# 48V-5V_Buck.net
KiCad netlist of a schematic drawn in Altium Designer
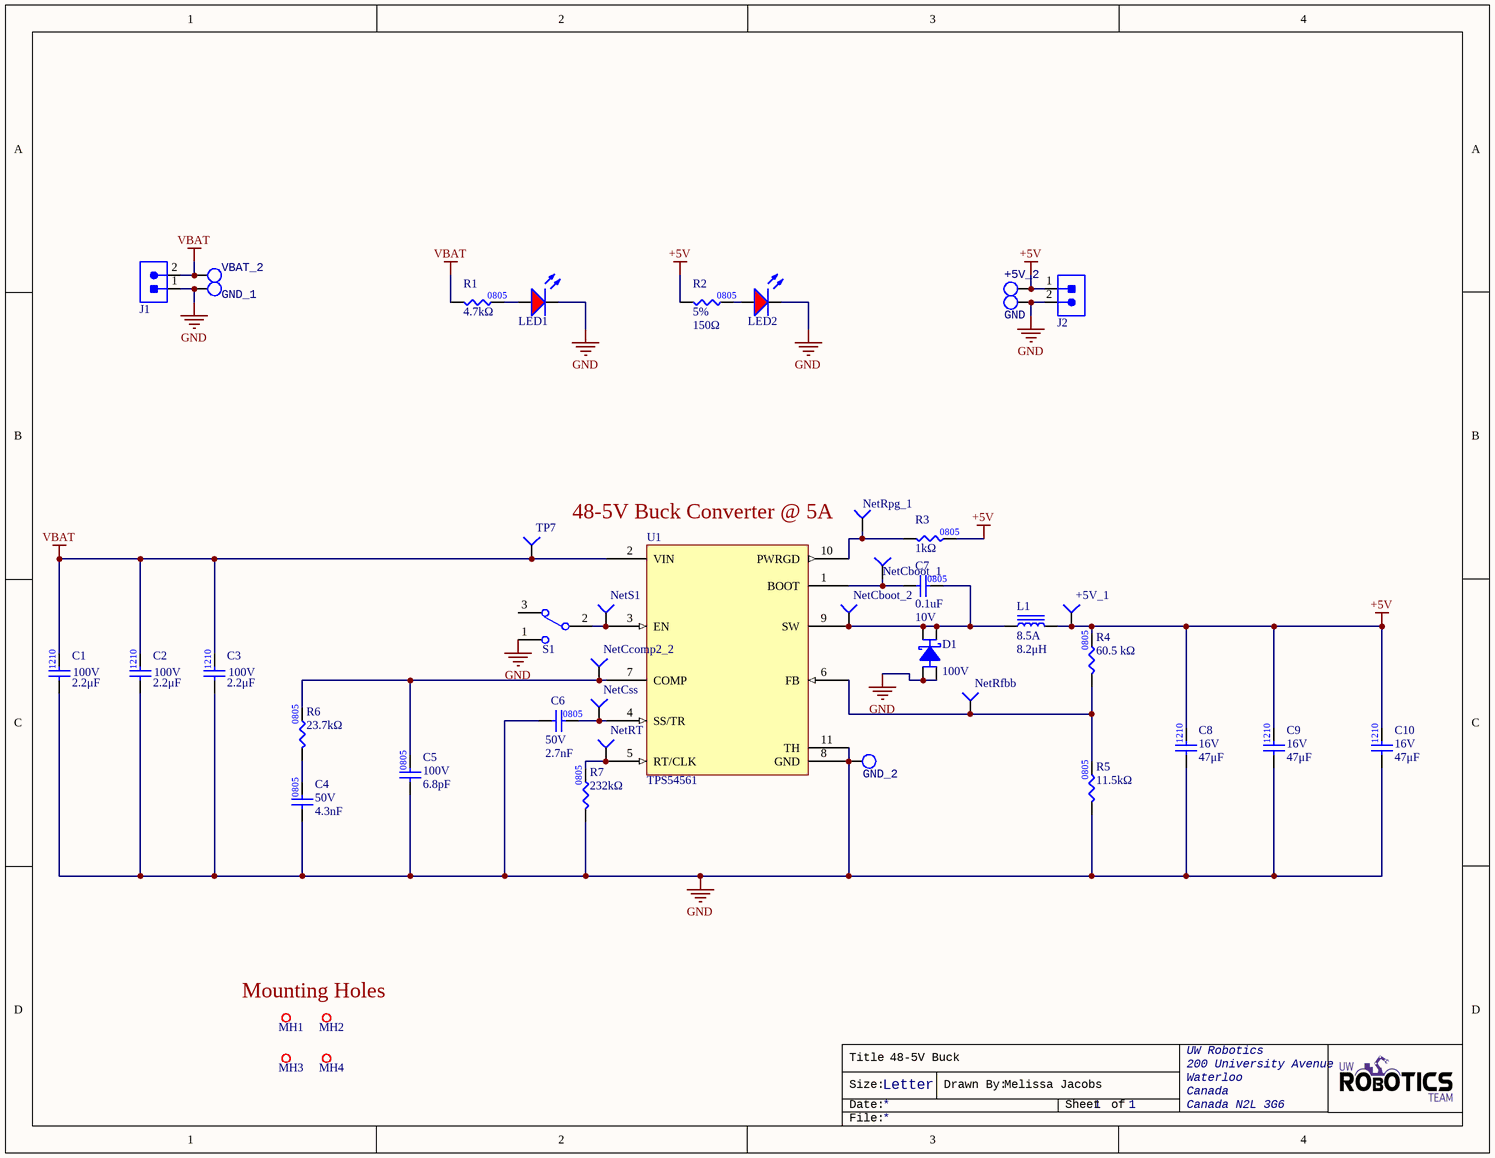
[diagram p0: 48V-5V Buck.SchDoc]

(export (version "E")
  (design (tool "Eeschema 10.0.6"))
  (components
    (comp (ref "+5V_1")
      (value "TESTPOINT_1MM_CIRCLE")
      (footprint "TESTPOINT_CIRCLE_1MM")
      (description "TESTPOINT 1MM CIRCLE")
      (libsource (lib "UWRT_Schematic_Library_2020") (part "TESTPOINT_1MM_CIRCLE"))
    )
    (comp (ref "+5V_2")
      (value "TESTPOINT_LOOP")
      (footprint "TESTPOINT_LOOP")
      (description "TESTPOINT THRUHOLE")
      (libsource (lib "UWRT_Schematic_Library_2020") (part "TESTPOINT_LOOP"))
    )
    (comp (ref "C1")
      (value "2.2μF")
      (footprint "CAPC3225X270N")
      (description "CAP CER 2.2UF 100V X7R 1210")
      (fields (field (name "VOLTAGE RATING") "100V") (field (name "Comment") "CAP_2.2uF_100V_1210_1"))
      (libsource (lib "UWRT_Schematic_Library_2020") (part "CAP_2.2uF_100V_1210_1"))
    )
    (comp (ref "C2")
      (value "2.2μF")
      (footprint "CAPC3225X270N")
      (description "CAP CER 2.2UF 100V X7R 1210")
      (fields (field (name "VOLTAGE RATING") "100V") (field (name "Comment") "CAP_2.2uF_100V_1210_1"))
      (libsource (lib "UWRT_Schematic_Library_2020") (part "CAP_2.2uF_100V_1210_1"))
    )
    (comp (ref "C3")
      (value "2.2μF")
      (footprint "CAPC3225X270N")
      (description "CAP CER 2.2UF 100V X7R 1210")
      (fields (field (name "VOLTAGE RATING") "100V") (field (name "Comment") "CAP_2.2uF_100V_1210_1"))
      (libsource (lib "UWRT_Schematic_Library_2020") (part "CAP_2.2uF_100V_1210_1"))
    )
    (comp (ref "C4")
      (value "4.3nF")
      (footprint "CAP2012")
      (description "CAP CER 4.3nF 50V C0G/NP0 0805")
      (fields (field (name "VOLTAGE RATING") "50V") (field (name "Comment") "CAP_4.3nF_50V_0805"))
      (libsource (lib "UWRT_Schematic_Library_2020") (part "CAP_4.3nF_50V_0805"))
    )
    (comp (ref "C5")
      (value "6.8pF")
      (footprint "CAP2012")
      (description "CAP CER 6.8pF 100V C0G/NP0 0805")
      (fields (field (name "VOLTAGE RATING") "100V") (field (name "Comment") "CAP_6.8pF_100V_0805_0.1pF"))
      (libsource (lib "UWRT_Schematic_Library_2020") (part "CAP_6.8pF_100V_0805_0.1pF"))
    )
    (comp (ref "C6")
      (value "2.7nF")
      (footprint "CAP0805")
      (description "CAP CER 2700PF 50V C0G 0805")
      (fields (field (name "VOLTAGE RATING") "50V") (field (name "Comment") "CAP_2.7nF_50V_0805"))
      (libsource (lib "UWRT_Schematic_Library_2020") (part "CAP_2.7nF_50V_0805"))
    )
    (comp (ref "C7")
      (value "0.1uF")
      (footprint "CAP0805")
      (description "CAP CER 0.1uF 10V 0805")
      (fields (field (name "VOLTAGE RATING") "10V") (field (name "Comment") "CAP_0.1uF_10V_0805"))
      (libsource (lib "UWRT_Schematic_Library_2020") (part "CAP_0.1uF_10V_0805"))
    )
    (comp (ref "C8")
      (value "47μF")
      (footprint "CAPC3225X270N")
      (description "CAP CER 47uF 16V X5R 1210")
      (fields (field (name "VOLTAGE RATING") "16V") (field (name "Comment") "CAP_47uF_16V_1210"))
      (libsource (lib "UWRT_Schematic_Library_2020") (part "CAP_47uF_16V_1210"))
    )
    (comp (ref "C9")
      (value "47μF")
      (footprint "CAPC3225X270N")
      (description "CAP CER 47uF 16V X5R 1210")
      (fields (field (name "VOLTAGE RATING") "16V") (field (name "Comment") "CAP_47uF_16V_1210"))
      (libsource (lib "UWRT_Schematic_Library_2020") (part "CAP_47uF_16V_1210"))
    )
    (comp (ref "C10")
      (value "47μF")
      (footprint "CAPC3225X270N")
      (description "CAP CER 47uF 16V X5R 1210")
      (fields (field (name "VOLTAGE RATING") "16V") (field (name "Comment") "CAP_47uF_16V_1210"))
      (libsource (lib "UWRT_Schematic_Library_2020") (part "CAP_47uF_16V_1210"))
    )
    (comp (ref "D1")
      (value "DIO_SCHOTTKY_100V_5.5A")
      (footprint "D-PAK")
      (description "DIODE SCHOTTKY 100V 5.5A DPAK")
      (fields (field (name "VR (MAX)") "100V"))
      (libsource (lib "UWRT_Schematic_Library_2020") (part "DIO_SCHOTTKY_100V_5.5A"))
    )
    (comp (ref "GND")
      (value "TESTPOINT_LOOP")
      (footprint "TESTPOINT_LOOP")
      (description "TESTPOINT THRUHOLE")
      (libsource (lib "UWRT_Schematic_Library_2020") (part "TESTPOINT_LOOP"))
    )
    (comp (ref "GND_1")
      (value "TESTPOINT_LOOP")
      (footprint "TESTPOINT_LOOP")
      (description "TESTPOINT THRUHOLE")
      (libsource (lib "UWRT_Schematic_Library_2020") (part "TESTPOINT_LOOP"))
    )
    (comp (ref "GND_2")
      (value "TESTPOINT_LOOP")
      (footprint "TESTPOINT_LOOP")
      (description "TESTPOINT THRUHOLE")
      (libsource (lib "UWRT_Schematic_Library_2020") (part "TESTPOINT_LOOP"))
    )
    (comp (ref "J1")
      (value "CON_2POS_SCREW_TERM")
      (footprint "1935161")
      (description "TERM BLK 2POS SIDE ENTRY 5MM")
      (libsource (lib "UWRT_Schematic_Library_2020") (part "CON_2POS_SCREW_TERM"))
    )
    (comp (ref "J2")
      (value "CON_2POS_SCREW_TERM")
      (footprint "1935161")
      (description "TERM BLK 2POS SIDE ENTRY 5MM")
      (libsource (lib "") (part "CON_2POS_SCREW_TERM_1"))
    )
    (comp (ref "L1")
      (value "8.2μH")
      (footprint "IND_8.2uH_8.5A")
      (description "FIXED IND 8.2UH 8.5A 28 MOHM SMD")
      (fields (field (name "CURRENT RATING") "8.5A") (field (name "Comment") "IND_8.2uH_8.5A"))
      (libsource (lib "UWRT_Schematic_Library_2020") (part "IND_8.2uH_8.5A"))
    )
    (comp (ref "LED1")
      (value "LED_RED")
      (footprint "LED_0805_RED")
      (description "LED RED DIFFUSED 0805 SMD")
      (libsource (lib "UWRT_Schematic_Library_2020") (part "LED_RED"))
    )
    (comp (ref "LED2")
      (value "LED_RED")
      (footprint "LED_0805_RED")
      (description "LED RED DIFFUSED 0805 SMD")
      (libsource (lib "UWRT_Schematic_Library_2020") (part "LED_RED"))
    )
    (comp (ref "MH1")
      (value "MOUNTING_HOLE_M3_GIMBAL_REV2")
      (footprint "MOUNTING_HOLE_3mm_GIMBAL_REV2")
      (description "MOUNTING_HOLE_M3 Gimbal Rev2")
      (libsource (lib "UWRT_Schematic_Library_2020") (part "MOUNTING_HOLE_M3_GIMBAL_REV2"))
    )
    (comp (ref "MH2")
      (value "MOUNTING_HOLE_M3_GIMBAL_REV2")
      (footprint "MOUNTING_HOLE_3mm_GIMBAL_REV2")
      (description "MOUNTING_HOLE_M3 Gimbal Rev2")
      (libsource (lib "UWRT_Schematic_Library_2020") (part "MOUNTING_HOLE_M3_GIMBAL_REV2"))
    )
    (comp (ref "MH3")
      (value "MOUNTING_HOLE_M3_GIMBAL_REV2")
      (footprint "MOUNTING_HOLE_3mm_GIMBAL_REV2")
      (description "MOUNTING_HOLE_M3 Gimbal Rev2")
      (libsource (lib "UWRT_Schematic_Library_2020") (part "MOUNTING_HOLE_M3_GIMBAL_REV2"))
    )
    (comp (ref "MH4")
      (value "MOUNTING_HOLE_M3_GIMBAL_REV2")
      (footprint "MOUNTING_HOLE_3mm_GIMBAL_REV2")
      (description "MOUNTING_HOLE_M3 Gimbal Rev2")
      (libsource (lib "UWRT_Schematic_Library_2020") (part "MOUNTING_HOLE_M3_GIMBAL_REV2"))
    )
    (comp (ref "NetCboot_1")
      (value "TESTPOINT_1MM_CIRCLE")
      (footprint "TESTPOINT_CIRCLE_1MM")
      (description "TESTPOINT 1MM CIRCLE")
      (libsource (lib "UWRT_Schematic_Library_2020") (part "TESTPOINT_1MM_CIRCLE"))
    )
    (comp (ref "NetCboot_2")
      (value "TESTPOINT_1MM_CIRCLE")
      (footprint "TESTPOINT_CIRCLE_1MM")
      (description "TESTPOINT 1MM CIRCLE")
      (libsource (lib "UWRT_Schematic_Library_2020") (part "TESTPOINT_1MM_CIRCLE"))
    )
    (comp (ref "NetCcomp2_2")
      (value "TESTPOINT_1MM_CIRCLE")
      (footprint "TESTPOINT_CIRCLE_1MM")
      (description "TESTPOINT 1MM CIRCLE")
      (libsource (lib "UWRT_Schematic_Library_2020") (part "TESTPOINT_1MM_CIRCLE"))
    )
    (comp (ref "NetCss")
      (value "TESTPOINT_1MM_CIRCLE")
      (footprint "TESTPOINT_CIRCLE_1MM")
      (description "TESTPOINT 1MM CIRCLE")
      (libsource (lib "UWRT_Schematic_Library_2020") (part "TESTPOINT_1MM_CIRCLE"))
    )
    (comp (ref "NetRfbb")
      (value "TESTPOINT_1MM_CIRCLE")
      (footprint "TESTPOINT_CIRCLE_1MM")
      (description "TESTPOINT 1MM CIRCLE")
      (libsource (lib "UWRT_Schematic_Library_2020") (part "TESTPOINT_1MM_CIRCLE"))
    )
    (comp (ref "NetRpg_1")
      (value "TESTPOINT_1MM_CIRCLE")
      (footprint "TESTPOINT_CIRCLE_1MM")
      (description "TESTPOINT 1MM CIRCLE")
      (libsource (lib "UWRT_Schematic_Library_2020") (part "TESTPOINT_1MM_CIRCLE"))
    )
    (comp (ref "NetRT")
      (value "TESTPOINT_1MM_CIRCLE")
      (footprint "TESTPOINT_CIRCLE_1MM")
      (description "TESTPOINT 1MM CIRCLE")
      (libsource (lib "UWRT_Schematic_Library_2020") (part "TESTPOINT_1MM_CIRCLE"))
    )
    (comp (ref "NetS1")
      (value "TESTPOINT_1MM_CIRCLE")
      (footprint "TESTPOINT_CIRCLE_1MM")
      (description "TESTPOINT 1MM CIRCLE")
      (libsource (lib "UWRT_Schematic_Library_2020") (part "TESTPOINT_1MM_CIRCLE"))
    )
    (comp (ref "R1")
      (value "4.7kΩ")
      (footprint "RES0805")
      (description "RES 4.7K OHM 5% 1/8W 0805")
      (fields (field (name "LCSC PART #") "C17673") (field (name "Comment") "RES_4.7kΩ_0805_5%"))
      (libsource (lib "UWRT_Schematic_Library_2020") (part "RES_4.7kΩ_0805_5%"))
    )
    (comp (ref "R2")
      (value "150Ω")
      (footprint "RES0805")
      (description "RES 150 OHM 5% 1/8W 0805")
      (fields (field (name "TOLERANCE") "5%") (field (name "Comment") "RES_150Ω_0805_5%"))
      (libsource (lib "UWRT_Schematic_Library_2020") (part "RES_150Ω_0805_5%"))
    )
    (comp (ref "R3")
      (value "1kΩ")
      (footprint "RES0805")
      (description "RES 1K OHM 1% 1/8W 0805")
      (fields (field (name "Comment") "RES_1kΩ_0805_1%"))
      (libsource (lib "UWRT_Schematic_Library_2020") (part "RES_1kΩ_0805_1%"))
    )
    (comp (ref "R4")
      (value "60.5 kΩ")
      (footprint "RES0805")
      (description "RES 60.5 kOHM 63 mW 0805")
      (fields (field (name "Comment") "RES_60.4kΩ_0805_1%"))
      (libsource (lib "UWRT_Schematic_Library_2020") (part "RES_60.4kΩ_0805_1%"))
    )
    (comp (ref "R5")
      (value "11.5kΩ")
      (footprint "RES0805")
      (description "RES 11.5K OHM 0.1% 1/10W 0805")
      (fields (field (name "Comment") "RES_11.5kΩ_0805_0.1%"))
      (libsource (lib "UWRT_Schematic_Library_2020") (part "RES_11.5kΩ_0805_0.1%"))
    )
    (comp (ref "R6")
      (value "23.7kΩ")
      (footprint "RES0805")
      (description "RES 1.07K OHM 1% 1/8W 0805")
      (fields (field (name "Comment") "RES_23.7kΩ_0805_1%"))
      (libsource (lib "UWRT_Schematic_Library_2020") (part "RES_23.7kΩ_0805_1%"))
    )
    (comp (ref "R7")
      (value "232kΩ")
      (footprint "RES0805")
      (description "RES 232K OHM 1% 1/8W 0805")
      (fields (field (name "LCSC PART #") "0") (field (name "Comment") "RES_232kΩ_0805_1%"))
      (libsource (lib "UWRT_Schematic_Library_2020") (part "RES_232kΩ_0805_1%"))
    )
    (comp (ref "S1")
      (value "SW_SLIDE_TOGGLE")
      (footprint "UWRT_Footprint_Library_2020:SW_SLIDE_TOGGLE")
      (description "SWITCH SLIDE SPDT 200MA 30V")
      (libsource (lib "UWRT_Schematic_Library_2020") (part "SW_SLIDE_TOGGLE"))
    )
    (comp (ref "TP7")
      (value "TESTPOINT_1MM_CIRCLE")
      (footprint "TESTPOINT_CIRCLE_1MM")
      (description "TESTPOINT 1MM CIRCLE")
      (libsource (lib "UWRT_Schematic_Library_2020") (part "TESTPOINT_1MM_CIRCLE"))
    )
    (comp (ref "U1")
      (value "TPS54561")
      (footprint "BUCK_TPS54561DPRR")
      (description "Buck Switching Regulator IC Positive Adjustable 0.8V 1 Output 5A 10-WDFN Exposed Pad")
      (libsource (lib "UWRT_Schematic_Library_2020") (part "TPS54561"))
    )
    (comp (ref "VBAT_2")
      (value "TESTPOINT_LOOP")
      (footprint "TESTPOINT_LOOP")
      (description "TESTPOINT THRUHOLE")
      (libsource (lib "UWRT_Schematic_Library_2020") (part "TESTPOINT_LOOP"))
    )
  )
  (nets
    (net (code "1") (name "+5V") (class "Default")
      (node (ref "+5V_1") (pin "1") (pinfunction "=value_1") (pintype "passive"))
      (node (ref "+5V_2") (pin "1") (pintype "passive"))
      (node (ref "C10") (pin "2") (pinfunction "2_2") (pintype "passive"))
      (node (ref "C8") (pin "2") (pinfunction "2_2") (pintype "passive"))
      (node (ref "C9") (pin "2") (pinfunction "2_2") (pintype "passive"))
      (node (ref "J2") (pin "1") (pinfunction "1_1") (pintype "passive"))
      (node (ref "L1") (pin "2") (pinfunction "2_2") (pintype "passive"))
      (node (ref "R2") (pin "1") (pinfunction "1_1") (pintype "passive"))
      (node (ref "R3") (pin "2") (pinfunction "2_2") (pintype "passive"))
      (node (ref "R4") (pin "2") (pinfunction "2_2") (pintype "passive"))
    )
    (net (code "2") (name "GND") (class "Default")
      (node (ref "C1") (pin "1") (pinfunction "1_1") (pintype "passive"))
      (node (ref "C10") (pin "1") (pinfunction "1_1") (pintype "passive"))
      (node (ref "C2") (pin "1") (pinfunction "1_1") (pintype "passive"))
      (node (ref "C3") (pin "1") (pinfunction "1_1") (pintype "passive"))
      (node (ref "C4") (pin "1") (pinfunction "1_1") (pintype "passive"))
      (node (ref "C5") (pin "1") (pinfunction "1_1") (pintype "passive"))
      (node (ref "C6") (pin "1") (pinfunction "1_1") (pintype "passive"))
      (node (ref "C8") (pin "1") (pinfunction "1_1") (pintype "passive"))
      (node (ref "C9") (pin "1") (pinfunction "1_1") (pintype "passive"))
      (node (ref "D1") (pin "1") (pinfunction "Anode_1") (pintype "passive"))
      (node (ref "D1") (pin "3") (pintype "passive"))
      (node (ref "GND") (pin "1") (pintype "passive"))
      (node (ref "GND_1") (pin "1") (pintype "passive"))
      (node (ref "GND_2") (pin "1") (pintype "passive"))
      (node (ref "J1") (pin "1") (pinfunction "1_1") (pintype "passive"))
      (node (ref "J2") (pin "2") (pinfunction "2_2") (pintype "passive"))
      (node (ref "LED1") (pin "2") (pinfunction "K_2") (pintype "passive"))
      (node (ref "LED2") (pin "2") (pinfunction "K_2") (pintype "passive"))
      (node (ref "R5") (pin "1") (pinfunction "1_1") (pintype "passive"))
      (node (ref "R7") (pin "1") (pinfunction "1_1") (pintype "passive"))
      (node (ref "S1") (pin "1") (pinfunction "1_1") (pintype "passive"))
      (node (ref "U1") (pin "11") (pinfunction "TH_11") (pintype "power_in"))
      (node (ref "U1") (pin "8") (pinfunction "GND_8") (pintype "power_in"))
    )
    (net (code "3") (name "Net-(C4-Pad2)") (class "Default")
      (node (ref "C4") (pin "2") (pinfunction "2_2") (pintype "passive"))
      (node (ref "R6") (pin "1") (pinfunction "1_1") (pintype "passive"))
    )
    (net (code "4") (name "Net-(D1-Cathode)") (class "Default")
      (node (ref "C7") (pin "2") (pinfunction "2_2") (pintype "passive"))
      (node (ref "D1") (pin "2") (pinfunction "Cathode_2") (pintype "passive"))
      (node (ref "D1") (pin "4") (pintype "passive"))
      (node (ref "L1") (pin "1") (pinfunction "1_1") (pintype "passive"))
      (node (ref "NetCboot_2") (pin "1") (pinfunction "=value_1") (pintype "passive"))
      (node (ref "U1") (pin "9") (pinfunction "SW_9") (pintype "power_in"))
    )
    (net (code "5") (name "Net-(LED1-A)") (class "Default")
      (node (ref "LED1") (pin "1") (pinfunction "A_1") (pintype "passive"))
      (node (ref "R1") (pin "2") (pinfunction "2_2") (pintype "passive"))
    )
    (net (code "6") (name "Net-(LED2-A)") (class "Default")
      (node (ref "LED2") (pin "1") (pinfunction "A_1") (pintype "passive"))
      (node (ref "R2") (pin "2") (pinfunction "2_2") (pintype "passive"))
    )
    (net (code "7") (name "Net-(NetCboot_1-=value)") (class "Default")
      (node (ref "C7") (pin "1") (pinfunction "1_1") (pintype "passive"))
      (node (ref "NetCboot_1") (pin "1") (pinfunction "=value_1") (pintype "passive"))
      (node (ref "U1") (pin "1") (pinfunction "BOOT_1") (pintype "power_in"))
    )
    (net (code "8") (name "Net-(NetCcomp2_2-=value)") (class "Default")
      (node (ref "C5") (pin "2") (pinfunction "2_2") (pintype "passive"))
      (node (ref "NetCcomp2_2") (pin "1") (pinfunction "=value_1") (pintype "passive"))
      (node (ref "R6") (pin "2") (pinfunction "2_2") (pintype "passive"))
      (node (ref "U1") (pin "7") (pinfunction "COMP_7") (pintype "power_in"))
    )
    (net (code "9") (name "Net-(NetCss-=value)") (class "Default")
      (node (ref "C6") (pin "2") (pinfunction "2_2") (pintype "passive"))
      (node (ref "NetCss") (pin "1") (pinfunction "=value_1") (pintype "passive"))
      (node (ref "U1") (pin "4") (pinfunction "SS/TR_4") (pintype "input"))
    )
    (net (code "10") (name "Net-(NetRT-=value)") (class "Default")
      (node (ref "NetRT") (pin "1") (pinfunction "=value_1") (pintype "passive"))
      (node (ref "R7") (pin "2") (pinfunction "2_2") (pintype "passive"))
      (node (ref "U1") (pin "5") (pinfunction "RT/CLK_5") (pintype "input"))
    )
    (net (code "11") (name "Net-(NetRfbb-=value)") (class "Default")
      (node (ref "NetRfbb") (pin "1") (pinfunction "=value_1") (pintype "passive"))
      (node (ref "R4") (pin "1") (pinfunction "1_1") (pintype "passive"))
      (node (ref "R5") (pin "2") (pinfunction "2_2") (pintype "passive"))
      (node (ref "U1") (pin "6") (pinfunction "FB_6") (pintype "input"))
    )
    (net (code "12") (name "Net-(NetRpg_1-=value)") (class "Default")
      (node (ref "NetRpg_1") (pin "1") (pinfunction "=value_1") (pintype "passive"))
      (node (ref "R3") (pin "1") (pinfunction "1_1") (pintype "passive"))
      (node (ref "U1") (pin "10") (pinfunction "PWRGD_10") (pintype "output"))
    )
    (net (code "13") (name "Net-(NetS1-=value)") (class "Default")
      (node (ref "NetS1") (pin "1") (pinfunction "=value_1") (pintype "passive"))
      (node (ref "S1") (pin "2") (pinfunction "2_2") (pintype "passive"))
      (node (ref "U1") (pin "3") (pinfunction "EN_3") (pintype "input"))
    )
    (net (code "14") (name "VBAT") (class "Default")
      (node (ref "C1") (pin "2") (pinfunction "2_2") (pintype "passive"))
      (node (ref "C2") (pin "2") (pinfunction "2_2") (pintype "passive"))
      (node (ref "C3") (pin "2") (pinfunction "2_2") (pintype "passive"))
      (node (ref "J1") (pin "2") (pinfunction "2_2") (pintype "passive"))
      (node (ref "R1") (pin "1") (pinfunction "1_1") (pintype "passive"))
      (node (ref "TP7") (pin "1") (pinfunction "=value_1") (pintype "passive"))
      (node (ref "U1") (pin "2") (pinfunction "VIN_2") (pintype "power_in"))
      (node (ref "VBAT_2") (pin "1") (pintype "passive"))
    )
    (net (code "15") (name "unconnected-(S1-Pad3)") (class "Default")
      (node (ref "S1") (pin "3") (pinfunction "3_3") (pintype "passive"))
    )
  )
)
